# DCCOMPProcess.net
KiCad netlist of a schematic drawn in Altium Designer
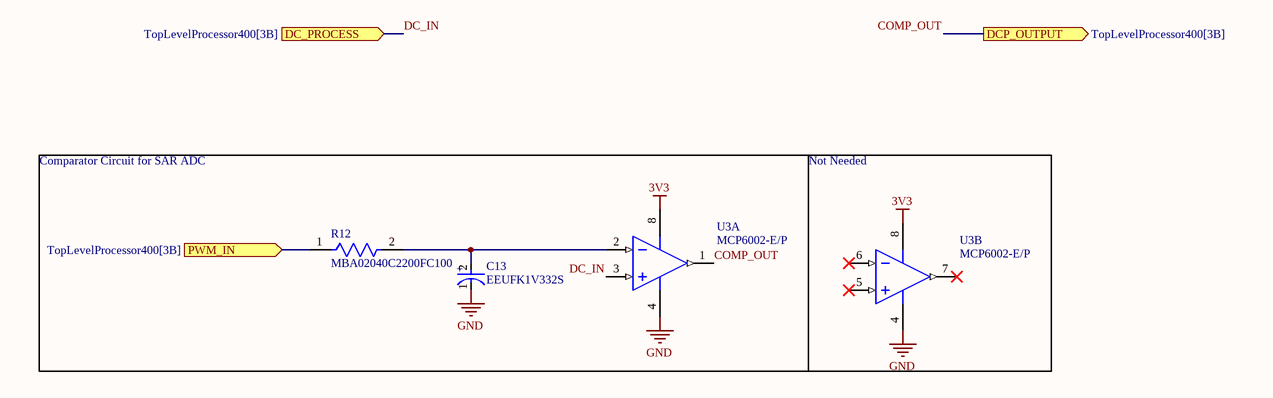
[diagram p0: DCCOMPProcess.SchDoc]

(export (version "E")
  (design (tool "Eeschema 10.0.6"))
  (components
    (comp (ref "C13")
      (value "EEUFK1V332S")
      (footprint "FP-RAD-TH-D_18_0_5-L_25_2-MFG")
      (description "Aluminum Electrolytic Capacitors (Radial Lead Type) AEC-Q200 Qualified 3300uF ±20% 35V")
      (fields (field (name "VOLTAGE") "35V") (field (name "TOLERANCE") "20%"))
      (libsource (lib "Altium Content Vault") (part "a00bbbee19879c290e62620ae7e47b1"))
    )
    (comp (ref "R12")
      (value "MBA02040C2200FC100")
      (footprint "FP-MBA0204-MFG")
      (description "RES 220 OHM 0.4W 1% AXIAL")
      (fields
        (field (name "OCTOPART") "https://octopart.com/mba02040c2200fc100-vishay-43743094")
        (field (name "MANUFACTURER") "Vishay BC Components")
      )
      (libsource (lib "Altium Content Vault") (part "1029c3af85768c4190bb7ad29bc67b5"))
    )
    (comp (ref "U3")
      (value "MCP6002-E/P")
      (footprint "PDIP300-P8")
      (description "None")
      (libsource (lib "Altium Content Vault") (part "AMP-OPA-MCP6002-IL8"))
    )
  )
  (nets
    (net (code "1") (name "/COMP_OUT") (class "Default")
      (node (ref "U3") (pin "1") (pinfunction "VOUTA_1") (pintype "output"))
    )
    (net (code "2") (name "/DC_IN") (class "Default")
      (node (ref "U3") (pin "3") (pinfunction "VINA+_3") (pintype "input"))
    )
    (net (code "3") (name "/PWM_IN") (class "Default")
      (node (ref "R12") (pin "1") (pinfunction "1_1") (pintype "passive"))
    )
    (net (code "4") (name "3V3") (class "Default")
      (node (ref "U3") (pin "8") (pinfunction "VDD_8") (pintype "power_in"))
    )
    (net (code "5") (name "GND") (class "Default")
      (node (ref "C13") (pin "1") (pinfunction "C_1") (pintype "passive"))
      (node (ref "U3") (pin "4") (pinfunction "VSS_4") (pintype "power_in"))
    )
    (net (code "6") (name "Net-(C13-A)") (class "Default")
      (node (ref "C13") (pin "2") (pinfunction "A_2") (pintype "passive"))
      (node (ref "R12") (pin "2") (pinfunction "2_2") (pintype "passive"))
      (node (ref "U3") (pin "2") (pinfunction "VINA-_2") (pintype "input"))
    )
    (net (code "7") (name "unconnected-(U3B-VINB+-Pad5)") (class "Default")
      (node (ref "U3") (pin "5") (pinfunction "VINB+_5") (pintype "input+no_connect"))
    )
    (net (code "8") (name "unconnected-(U3B-VINB--Pad6)") (class "Default")
      (node (ref "U3") (pin "6") (pinfunction "VINB-_6") (pintype "input+no_connect"))
    )
    (net (code "9") (name "unconnected-(U3B-VOUTB-Pad7)") (class "Default")
      (node (ref "U3") (pin "7") (pinfunction "VOUTB_7") (pintype "output+no_connect"))
    )
  )
)
